# vertical_farming.net
KiCad netlist of a schematic drawn in EAGLE
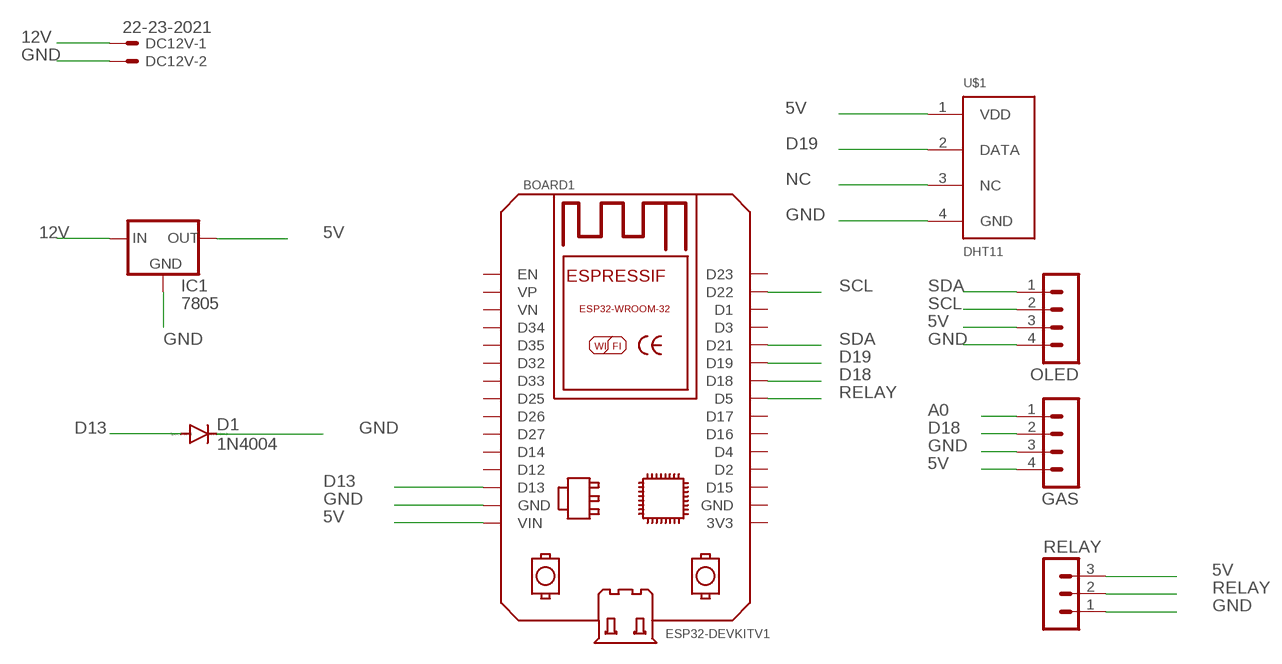
[diagram p0: schematic, sheet 1]

(export (version "E")
  (design (tool "Eeschema 10.0.6"))
  (components
    (comp (ref "BOARD1")
      (value "ESP32DEVKITV1")
      (footprint "eagle-import:ESP32-DEVKITV1")
      (libsource (lib "eagle-import") (part "ESP32DEVKITV1"))
    )
    (comp (ref "D1")
      (value "1N4004")
      (footprint "eagle-import:DO41-10")
      (libsource (lib "eagle-import") (part "1N4004"))
    )
    (comp (ref "DC12V")
      (value "22-23-2021")
      (footprint "eagle-import:22-23-2021")
      (fields (field (name "MF") "MOLEX"))
      (libsource (lib "eagle-import") (part "22-23-2021"))
    )
    (comp (ref "GAS")
      (value "MA04-1")
      (footprint "eagle-import:MA04-1")
      (libsource (lib "eagle-import") (part "MA04-1"))
    )
    (comp (ref "IC1")
      (value "7805")
      (footprint "eagle-import:78XXL")
      (libsource (lib "eagle-import") (part "78XXL"))
    )
    (comp (ref "OLED")
      (value "MA04-1")
      (footprint "eagle-import:MA04-1")
      (libsource (lib "eagle-import") (part "MA04-1"))
    )
    (comp (ref "RELAY")
      (value "MA03-1")
      (footprint "eagle-import:MA03-1")
      (libsource (lib "eagle-import") (part "MA03-1"))
    )
    (comp (ref "U$1")
      (value "DHT11")
      (footprint "eagle-import:DHT11")
      (libsource (lib "eagle-import") (part "DHT11"))
    )
  )
  (nets
    (net (code "1") (name "/5V") (class "Default")
      (node (ref "BOARD1") (pin "VIN") (pinfunction "VIN_VIN") (pintype "bidirectional"))
      (node (ref "GAS") (pin "4") (pinfunction "4_4") (pintype "passive"))
      (node (ref "IC1") (pin "OUT") (pinfunction "OUT_OUT") (pintype "passive"))
      (node (ref "OLED") (pin "3") (pinfunction "3_3") (pintype "passive"))
      (node (ref "RELAY") (pin "3") (pinfunction "3_3") (pintype "passive"))
      (node (ref "U$1") (pin "1") (pinfunction "VDD_1") (pintype "power_in"))
    )
    (net (code "2") (name "/12V") (class "Default")
      (node (ref "DC12V") (pin "1") (pinfunction "S_1") (pintype "passive"))
      (node (ref "IC1") (pin "IN") (pinfunction "IN_IN") (pintype "input"))
    )
    (net (code "3") (name "/A0") (class "Default")
      (node (ref "GAS") (pin "1") (pinfunction "1_1") (pintype "passive"))
    )
    (net (code "4") (name "/D13") (class "Default")
      (node (ref "BOARD1") (pin "D13") (pinfunction "D13_D13") (pintype "bidirectional"))
      (node (ref "D1") (pin "A") (pinfunction "A_A") (pintype "passive"))
    )
    (net (code "5") (name "/D18") (class "Default")
      (node (ref "BOARD1") (pin "D18") (pinfunction "D18_D18") (pintype "bidirectional"))
      (node (ref "GAS") (pin "2") (pinfunction "2_2") (pintype "passive"))
    )
    (net (code "6") (name "/D19") (class "Default")
      (node (ref "BOARD1") (pin "D19") (pinfunction "D19_D19") (pintype "bidirectional"))
      (node (ref "U$1") (pin "2") (pinfunction "DATA_2") (pintype "bidirectional"))
    )
    (net (code "7") (name "/GND") (class "Default")
      (node (ref "BOARD1") (pin "GND") (pinfunction "GND_GND") (pintype "bidirectional"))
      (node (ref "D1") (pin "C") (pinfunction "C_C") (pintype "passive"))
      (node (ref "DC12V") (pin "2") (pinfunction "S_2") (pintype "passive"))
      (node (ref "GAS") (pin "3") (pinfunction "3_3") (pintype "passive"))
      (node (ref "IC1") (pin "GND") (pinfunction "GND_GND") (pintype "input"))
      (node (ref "OLED") (pin "4") (pinfunction "4_4") (pintype "passive"))
      (node (ref "RELAY") (pin "1") (pinfunction "1_1") (pintype "passive"))
      (node (ref "U$1") (pin "4") (pinfunction "GND_4") (pintype "power_in"))
    )
    (net (code "8") (name "/NC") (class "Default")
      (node (ref "U$1") (pin "3") (pinfunction "NC_3") (pintype "bidirectional"))
    )
    (net (code "9") (name "/RELAY") (class "Default")
      (node (ref "BOARD1") (pin "D5") (pinfunction "D5_D5") (pintype "bidirectional"))
      (node (ref "RELAY") (pin "2") (pinfunction "2_2") (pintype "passive"))
    )
    (net (code "10") (name "/SCL") (class "Default")
      (node (ref "BOARD1") (pin "D22") (pinfunction "D22_D22") (pintype "bidirectional"))
      (node (ref "OLED") (pin "2") (pinfunction "2_2") (pintype "passive"))
    )
    (net (code "11") (name "/SDA") (class "Default")
      (node (ref "BOARD1") (pin "D21") (pinfunction "D21_D21") (pintype "bidirectional"))
      (node (ref "OLED") (pin "1") (pinfunction "1_1") (pintype "passive"))
    )
    (net (code "12") (name "unconnected-(BOARD1-GND-PadGND@1)") (class "Default")
      (node (ref "BOARD1") (pin "GND@1") (pinfunction "GND_GND@1") (pintype "bidirectional"))
    )
    (net (code "13") (name "unconnected-(BOARD1-Pad3V3)") (class "Default")
      (node (ref "BOARD1") (pin "3V3") (pinfunction "3V3_3V3") (pintype "bidirectional"))
    )
    (net (code "14") (name "unconnected-(BOARD1-PadD1)") (class "Default")
      (node (ref "BOARD1") (pin "D1") (pinfunction "D1_D1") (pintype "bidirectional"))
    )
    (net (code "15") (name "unconnected-(BOARD1-PadD2)") (class "Default")
      (node (ref "BOARD1") (pin "D2") (pinfunction "D2_D2") (pintype "bidirectional"))
    )
    (net (code "16") (name "unconnected-(BOARD1-PadD3)") (class "Default")
      (node (ref "BOARD1") (pin "D3") (pinfunction "D3_D3") (pintype "bidirectional"))
    )
    (net (code "17") (name "unconnected-(BOARD1-PadD4)") (class "Default")
      (node (ref "BOARD1") (pin "D4") (pinfunction "D4_D4") (pintype "bidirectional"))
    )
    (net (code "18") (name "unconnected-(BOARD1-PadD12)") (class "Default")
      (node (ref "BOARD1") (pin "D12") (pinfunction "D12_D12") (pintype "bidirectional"))
    )
    (net (code "19") (name "unconnected-(BOARD1-PadD14)") (class "Default")
      (node (ref "BOARD1") (pin "D14") (pinfunction "D14_D14") (pintype "bidirectional"))
    )
    (net (code "20") (name "unconnected-(BOARD1-PadD15)") (class "Default")
      (node (ref "BOARD1") (pin "D15") (pinfunction "D15_D15") (pintype "bidirectional"))
    )
    (net (code "21") (name "unconnected-(BOARD1-PadD16)") (class "Default")
      (node (ref "BOARD1") (pin "D16") (pinfunction "D16_D16") (pintype "bidirectional"))
    )
    (net (code "22") (name "unconnected-(BOARD1-PadD17)") (class "Default")
      (node (ref "BOARD1") (pin "D17") (pinfunction "D17_D17") (pintype "bidirectional"))
    )
    (net (code "23") (name "unconnected-(BOARD1-PadD23)") (class "Default")
      (node (ref "BOARD1") (pin "D23") (pinfunction "D23_D23") (pintype "bidirectional"))
    )
    (net (code "24") (name "unconnected-(BOARD1-PadD25)") (class "Default")
      (node (ref "BOARD1") (pin "D25") (pinfunction "D25_D25") (pintype "bidirectional"))
    )
    (net (code "25") (name "unconnected-(BOARD1-PadD26)") (class "Default")
      (node (ref "BOARD1") (pin "D26") (pinfunction "D26_D26") (pintype "bidirectional"))
    )
    (net (code "26") (name "unconnected-(BOARD1-PadD27)") (class "Default")
      (node (ref "BOARD1") (pin "D27") (pinfunction "D27_D27") (pintype "bidirectional"))
    )
    (net (code "27") (name "unconnected-(BOARD1-PadD32)") (class "Default")
      (node (ref "BOARD1") (pin "D32") (pinfunction "D32_D32") (pintype "bidirectional"))
    )
    (net (code "28") (name "unconnected-(BOARD1-PadD33)") (class "Default")
      (node (ref "BOARD1") (pin "D33") (pinfunction "D33_D33") (pintype "bidirectional"))
    )
    (net (code "29") (name "unconnected-(BOARD1-PadD34)") (class "Default")
      (node (ref "BOARD1") (pin "D34") (pinfunction "D34_D34") (pintype "bidirectional"))
    )
    (net (code "30") (name "unconnected-(BOARD1-PadD35)") (class "Default")
      (node (ref "BOARD1") (pin "D35") (pinfunction "D35_D35") (pintype "bidirectional"))
    )
    (net (code "31") (name "unconnected-(BOARD1-PadEN)") (class "Default")
      (node (ref "BOARD1") (pin "EN") (pinfunction "EN_EN") (pintype "bidirectional"))
    )
    (net (code "32") (name "unconnected-(BOARD1-PadVN)") (class "Default")
      (node (ref "BOARD1") (pin "VN") (pinfunction "VN_VN") (pintype "bidirectional"))
    )
    (net (code "33") (name "unconnected-(BOARD1-PadVP)") (class "Default")
      (node (ref "BOARD1") (pin "VP") (pinfunction "VP_VP") (pintype "bidirectional"))
    )
  )
)
